# U2S_XLAT.net
KiCad netlist of a schematic drawn in Altium Designer
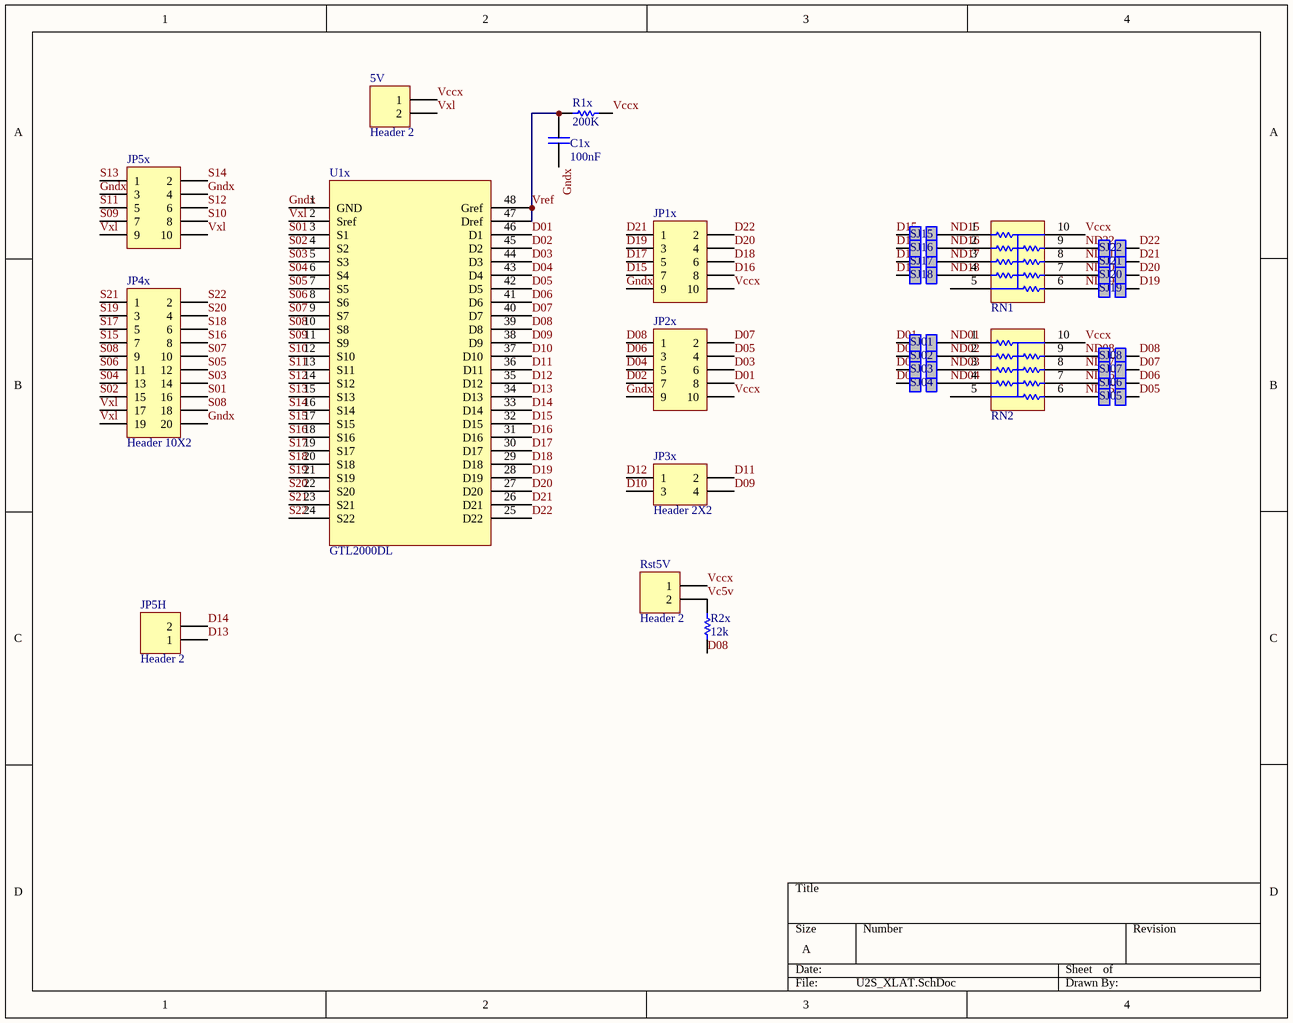
[diagram p0: U2S_XLAT.SchDoc]

(export (version "E")
  (design (tool "Eeschema 10.0.6"))
  (components
    (comp (ref "5V")
      (value "Header 2")
      (footprint "HDR1X2")
      (description "Header, 2-Pin")
      (fields (field (name "PUBLISHER") "Altium Limited"))
      (libsource (lib "") (part "Header 2_1"))
    )
    (comp (ref "C1x")
      (value "100nF")
      (footprint "SMD0603")
      (fields (field (name "Comment") "Capacitor"))
      (libsource (lib "MiscComponents") (part "Capacitor"))
    )
    (comp (ref "JP1x")
      (value "Header 5X2")
      (footprint "HDR2X5")
      (description "Header, 5-Pin, Dual row")
      (fields (field (name "PUBLISHER") "Altium Limited"))
      (libsource (lib "Miscellaneous Connectors") (part "Header 5X2"))
    )
    (comp (ref "JP2x")
      (value "Header 5X2")
      (footprint "HDR2X5")
      (description "Header, 5-Pin, Dual row")
      (fields (field (name "PUBLISHER") "Altium Limited"))
      (libsource (lib "Miscellaneous Connectors") (part "Header 5X2"))
    )
    (comp (ref "JP3x")
      (value "Header 2X2")
      (footprint "HDR2X2")
      (description "Header, 2-Pin, Dual row")
      (fields (field (name "PUBLISHER") "Altium Limited"))
      (libsource (lib "Miscellaneous Connectors") (part "Header 2X2"))
    )
    (comp (ref "JP4x")
      (value "Header 10X2")
      (footprint "HDR2X10")
      (description "Header, 10-Pin, Dual row")
      (fields (field (name "PUBLISHER") "Altium Limited"))
      (libsource (lib "Miscellaneous Connectors") (part "Header 10X2"))
    )
    (comp (ref "JP5H")
      (value "Header 2")
      (footprint "HDR1X2")
      (description "Header, 2-Pin")
      (fields (field (name "PUBLISHER") "Altium Limited"))
      (libsource (lib "Miscellaneous Connectors") (part "Header 2"))
    )
    (comp (ref "JP5x")
      (value "Header 5X2")
      (footprint "HDR2X5")
      (description "Header, 5-Pin, Dual row")
      (fields (field (name "PUBLISHER") "Altium Limited"))
      (libsource (lib "Miscellaneous Connectors") (part "Header 5X2"))
    )
    (comp (ref "R1x")
      (value "200K")
      (footprint "SMD0805")
      (fields (field (name "Comment") "Resistor"))
      (libsource (lib "MiscComponents") (part "Resistor"))
    )
    (comp (ref "R2x")
      (value "12k")
      (footprint "SMD0603")
      (fields (field (name "Comment") "Resistor"))
      (libsource (lib "MiscComponents") (part "Resistor"))
    )
    (comp (ref "RN1") (value "YC158") (footprint "YC158") (libsource (lib "MiscComponents") (part "YC158")))
    (comp (ref "RN2") (value "YC158") (footprint "YC158") (libsource (lib "MiscComponents") (part "YC158")))
    (comp (ref "Rst5V")
      (value "Header 2")
      (footprint "HDR1X2")
      (description "Header, 2-Pin")
      (fields (field (name "PUBLISHER") "Altium Limited"))
      (libsource (lib "") (part "Header 2_1"))
    )
    (comp (ref "SJ01")
      (value "Jumper")
      (footprint "Jumper")
      (description "Solder Jumper")
      (libsource (lib "MiscComponents") (part "Jumper"))
    )
    (comp (ref "SJ02")
      (value "Jumper")
      (footprint "Jumper")
      (description "Solder Jumper")
      (libsource (lib "MiscComponents") (part "Jumper"))
    )
    (comp (ref "SJ03")
      (value "Jumper")
      (footprint "Jumper")
      (description "Solder Jumper")
      (libsource (lib "MiscComponents") (part "Jumper"))
    )
    (comp (ref "SJ04")
      (value "Jumper")
      (footprint "Jumper")
      (description "Solder Jumper")
      (libsource (lib "MiscComponents") (part "Jumper"))
    )
    (comp (ref "SJ05")
      (value "Jumper")
      (footprint "Jumper")
      (description "Solder Jumper")
      (libsource (lib "MiscComponents") (part "Jumper"))
    )
    (comp (ref "SJ06")
      (value "Jumper")
      (footprint "Jumper")
      (description "Solder Jumper")
      (libsource (lib "MiscComponents") (part "Jumper"))
    )
    (comp (ref "SJ07")
      (value "Jumper")
      (footprint "Jumper")
      (description "Solder Jumper")
      (libsource (lib "MiscComponents") (part "Jumper"))
    )
    (comp (ref "SJ08")
      (value "Jumper")
      (footprint "Jumper")
      (description "Solder Jumper")
      (libsource (lib "MiscComponents") (part "Jumper"))
    )
    (comp (ref "SJ15")
      (value "Jumper")
      (footprint "Jumper")
      (description "Solder Jumper")
      (libsource (lib "MiscComponents") (part "Jumper"))
    )
    (comp (ref "SJ16")
      (value "Jumper")
      (footprint "Jumper")
      (description "Solder Jumper")
      (libsource (lib "MiscComponents") (part "Jumper"))
    )
    (comp (ref "SJ17")
      (value "Jumper")
      (footprint "Jumper")
      (description "Solder Jumper")
      (libsource (lib "MiscComponents") (part "Jumper"))
    )
    (comp (ref "SJ18")
      (value "Jumper")
      (footprint "Jumper")
      (description "Solder Jumper")
      (libsource (lib "MiscComponents") (part "Jumper"))
    )
    (comp (ref "SJ19")
      (value "Jumper")
      (footprint "Jumper")
      (description "Solder Jumper")
      (libsource (lib "MiscComponents") (part "Jumper"))
    )
    (comp (ref "SJ20")
      (value "Jumper")
      (footprint "Jumper")
      (description "Solder Jumper")
      (libsource (lib "MiscComponents") (part "Jumper"))
    )
    (comp (ref "SJ21")
      (value "Jumper")
      (footprint "Jumper")
      (description "Solder Jumper")
      (libsource (lib "MiscComponents") (part "Jumper"))
    )
    (comp (ref "SJ22")
      (value "Jumper")
      (footprint "Jumper")
      (description "Solder Jumper")
      (libsource (lib "MiscComponents") (part "Jumper"))
    )
    (comp (ref "U1x")
      (value "GTL2000DL")
      (footprint "SSOP48")
      (libsource (lib "MiscComponents") (part "GTL2000DL"))
    )
  )
  (nets
    (net (code "1") (name "/D01") (class "Default")
      (node (ref "JP2x") (pin "8") (pinfunction "8_8") (pintype "passive"))
      (node (ref "SJ01") (pin "2") (pinfunction "2_2") (pintype "passive"))
      (node (ref "U1x") (pin "46") (pinfunction "D1_46") (pintype "passive"))
    )
    (net (code "2") (name "/D02") (class "Default")
      (node (ref "JP2x") (pin "7") (pinfunction "7_7") (pintype "passive"))
      (node (ref "SJ02") (pin "2") (pinfunction "2_2") (pintype "passive"))
      (node (ref "U1x") (pin "45") (pinfunction "D2_45") (pintype "passive"))
    )
    (net (code "3") (name "/D03") (class "Default")
      (node (ref "JP2x") (pin "6") (pinfunction "6_6") (pintype "passive"))
      (node (ref "SJ03") (pin "2") (pinfunction "2_2") (pintype "passive"))
      (node (ref "U1x") (pin "44") (pinfunction "D3_44") (pintype "passive"))
    )
    (net (code "4") (name "/D04") (class "Default")
      (node (ref "JP2x") (pin "5") (pinfunction "5_5") (pintype "passive"))
      (node (ref "SJ04") (pin "2") (pinfunction "2_2") (pintype "passive"))
      (node (ref "U1x") (pin "43") (pinfunction "D4_43") (pintype "passive"))
    )
    (net (code "5") (name "/D05") (class "Default")
      (node (ref "JP2x") (pin "4") (pinfunction "4_4") (pintype "passive"))
      (node (ref "SJ05") (pin "2") (pinfunction "2_2") (pintype "passive"))
      (node (ref "U1x") (pin "42") (pinfunction "D5_42") (pintype "passive"))
    )
    (net (code "6") (name "/D06") (class "Default")
      (node (ref "JP2x") (pin "3") (pinfunction "3_3") (pintype "passive"))
      (node (ref "SJ06") (pin "2") (pinfunction "2_2") (pintype "passive"))
      (node (ref "U1x") (pin "41") (pinfunction "D6_41") (pintype "passive"))
    )
    (net (code "7") (name "/D07") (class "Default")
      (node (ref "JP2x") (pin "2") (pinfunction "2_2") (pintype "passive"))
      (node (ref "SJ07") (pin "2") (pinfunction "2_2") (pintype "passive"))
      (node (ref "U1x") (pin "40") (pinfunction "D7_40") (pintype "passive"))
    )
    (net (code "8") (name "/D08") (class "Default")
      (node (ref "JP2x") (pin "1") (pinfunction "1_1") (pintype "passive"))
      (node (ref "R2x") (pin "1") (pinfunction "1_1") (pintype "passive"))
      (node (ref "SJ08") (pin "2") (pinfunction "2_2") (pintype "passive"))
      (node (ref "U1x") (pin "39") (pinfunction "D8_39") (pintype "passive"))
    )
    (net (code "9") (name "/D09") (class "Default")
      (node (ref "JP3x") (pin "4") (pinfunction "4_4") (pintype "passive"))
      (node (ref "U1x") (pin "38") (pinfunction "D9_38") (pintype "passive"))
    )
    (net (code "10") (name "/D10") (class "Default")
      (node (ref "JP3x") (pin "3") (pinfunction "3_3") (pintype "passive"))
      (node (ref "U1x") (pin "37") (pinfunction "D10_37") (pintype "passive"))
    )
    (net (code "11") (name "/D11") (class "Default")
      (node (ref "JP3x") (pin "2") (pinfunction "2_2") (pintype "passive"))
      (node (ref "U1x") (pin "36") (pinfunction "D11_36") (pintype "passive"))
    )
    (net (code "12") (name "/D12") (class "Default")
      (node (ref "JP3x") (pin "1") (pinfunction "1_1") (pintype "passive"))
      (node (ref "U1x") (pin "35") (pinfunction "D12_35") (pintype "passive"))
    )
    (net (code "13") (name "/D13") (class "Default")
      (node (ref "JP5H") (pin "1") (pinfunction "1_1") (pintype "passive"))
      (node (ref "U1x") (pin "34") (pinfunction "D13_34") (pintype "passive"))
    )
    (net (code "14") (name "/D14") (class "Default")
      (node (ref "JP5H") (pin "2") (pinfunction "2_2") (pintype "passive"))
      (node (ref "U1x") (pin "33") (pinfunction "D14_33") (pintype "passive"))
    )
    (net (code "15") (name "/D15") (class "Default")
      (node (ref "JP1x") (pin "7") (pinfunction "7_7") (pintype "passive"))
      (node (ref "SJ15") (pin "2") (pinfunction "2_2") (pintype "passive"))
      (node (ref "U1x") (pin "32") (pinfunction "D15_32") (pintype "passive"))
    )
    (net (code "16") (name "/D16") (class "Default")
      (node (ref "JP1x") (pin "8") (pinfunction "8_8") (pintype "passive"))
      (node (ref "SJ16") (pin "2") (pinfunction "2_2") (pintype "passive"))
      (node (ref "U1x") (pin "31") (pinfunction "D16_31") (pintype "passive"))
    )
    (net (code "17") (name "/D17") (class "Default")
      (node (ref "JP1x") (pin "5") (pinfunction "5_5") (pintype "passive"))
      (node (ref "SJ17") (pin "2") (pinfunction "2_2") (pintype "passive"))
      (node (ref "U1x") (pin "30") (pinfunction "D17_30") (pintype "passive"))
    )
    (net (code "18") (name "/D18") (class "Default")
      (node (ref "JP1x") (pin "6") (pinfunction "6_6") (pintype "passive"))
      (node (ref "SJ18") (pin "2") (pinfunction "2_2") (pintype "passive"))
      (node (ref "U1x") (pin "29") (pinfunction "D18_29") (pintype "passive"))
    )
    (net (code "19") (name "/D19") (class "Default")
      (node (ref "JP1x") (pin "3") (pinfunction "3_3") (pintype "passive"))
      (node (ref "SJ19") (pin "2") (pinfunction "2_2") (pintype "passive"))
      (node (ref "U1x") (pin "28") (pinfunction "D19_28") (pintype "passive"))
    )
    (net (code "20") (name "/D20") (class "Default")
      (node (ref "JP1x") (pin "4") (pinfunction "4_4") (pintype "passive"))
      (node (ref "SJ20") (pin "2") (pinfunction "2_2") (pintype "passive"))
      (node (ref "U1x") (pin "27") (pinfunction "D20_27") (pintype "passive"))
    )
    (net (code "21") (name "/D21") (class "Default")
      (node (ref "JP1x") (pin "1") (pinfunction "1_1") (pintype "passive"))
      (node (ref "SJ21") (pin "2") (pinfunction "2_2") (pintype "passive"))
      (node (ref "U1x") (pin "26") (pinfunction "D21_26") (pintype "passive"))
    )
    (net (code "22") (name "/D22") (class "Default")
      (node (ref "JP1x") (pin "2") (pinfunction "2_2") (pintype "passive"))
      (node (ref "SJ22") (pin "2") (pinfunction "2_2") (pintype "passive"))
      (node (ref "U1x") (pin "25") (pinfunction "D22_25") (pintype "passive"))
    )
    (net (code "23") (name "/Gndx") (class "Default")
      (node (ref "C1x") (pin "1") (pinfunction "1_1") (pintype "passive"))
      (node (ref "JP1x") (pin "9") (pinfunction "9_9") (pintype "passive"))
      (node (ref "JP2x") (pin "9") (pinfunction "9_9") (pintype "passive"))
      (node (ref "JP4x") (pin "20") (pinfunction "20_20") (pintype "passive"))
      (node (ref "JP5x") (pin "3") (pinfunction "3_3") (pintype "passive"))
      (node (ref "JP5x") (pin "4") (pinfunction "4_4") (pintype "passive"))
      (node (ref "U1x") (pin "1") (pinfunction "GND_1") (pintype "passive"))
    )
    (net (code "24") (name "/ND01") (class "Default")
      (node (ref "RN2") (pin "1") (pinfunction "1_1") (pintype "passive"))
      (node (ref "SJ01") (pin "1") (pinfunction "1_1") (pintype "passive"))
    )
    (net (code "25") (name "/ND02") (class "Default")
      (node (ref "RN2") (pin "2") (pinfunction "2_2") (pintype "passive"))
      (node (ref "SJ02") (pin "1") (pinfunction "1_1") (pintype "passive"))
    )
    (net (code "26") (name "/ND03") (class "Default")
      (node (ref "RN2") (pin "3") (pinfunction "3_3") (pintype "passive"))
      (node (ref "SJ03") (pin "1") (pinfunction "1_1") (pintype "passive"))
    )
    (net (code "27") (name "/ND04") (class "Default")
      (node (ref "RN2") (pin "4") (pinfunction "4_4") (pintype "passive"))
      (node (ref "SJ04") (pin "1") (pinfunction "1_1") (pintype "passive"))
    )
    (net (code "28") (name "/ND05") (class "Default")
      (node (ref "RN2") (pin "6") (pinfunction "6_6") (pintype "passive"))
      (node (ref "SJ05") (pin "1") (pinfunction "1_1") (pintype "passive"))
    )
    (net (code "29") (name "/ND06") (class "Default")
      (node (ref "RN2") (pin "7") (pinfunction "7_7") (pintype "passive"))
      (node (ref "SJ06") (pin "1") (pinfunction "1_1") (pintype "passive"))
    )
    (net (code "30") (name "/ND07") (class "Default")
      (node (ref "RN2") (pin "8") (pinfunction "8_8") (pintype "passive"))
      (node (ref "SJ07") (pin "1") (pinfunction "1_1") (pintype "passive"))
    )
    (net (code "31") (name "/ND08") (class "Default")
      (node (ref "RN2") (pin "9") (pinfunction "9_9") (pintype "passive"))
      (node (ref "SJ08") (pin "1") (pinfunction "1_1") (pintype "passive"))
    )
    (net (code "32") (name "/ND15") (class "Default")
      (node (ref "RN1") (pin "1") (pinfunction "1_1") (pintype "passive"))
      (node (ref "SJ15") (pin "1") (pinfunction "1_1") (pintype "passive"))
    )
    (net (code "33") (name "/ND16") (class "Default")
      (node (ref "RN1") (pin "2") (pinfunction "2_2") (pintype "passive"))
      (node (ref "SJ16") (pin "1") (pinfunction "1_1") (pintype "passive"))
    )
    (net (code "34") (name "/ND17") (class "Default")
      (node (ref "RN1") (pin "3") (pinfunction "3_3") (pintype "passive"))
      (node (ref "SJ17") (pin "1") (pinfunction "1_1") (pintype "passive"))
    )
    (net (code "35") (name "/ND18") (class "Default")
      (node (ref "RN1") (pin "4") (pinfunction "4_4") (pintype "passive"))
      (node (ref "SJ18") (pin "1") (pinfunction "1_1") (pintype "passive"))
    )
    (net (code "36") (name "/ND19") (class "Default")
      (node (ref "RN1") (pin "6") (pinfunction "6_6") (pintype "passive"))
      (node (ref "SJ19") (pin "1") (pinfunction "1_1") (pintype "passive"))
    )
    (net (code "37") (name "/ND20") (class "Default")
      (node (ref "RN1") (pin "7") (pinfunction "7_7") (pintype "passive"))
      (node (ref "SJ20") (pin "1") (pinfunction "1_1") (pintype "passive"))
    )
    (net (code "38") (name "/ND21") (class "Default")
      (node (ref "RN1") (pin "8") (pinfunction "8_8") (pintype "passive"))
      (node (ref "SJ21") (pin "1") (pinfunction "1_1") (pintype "passive"))
    )
    (net (code "39") (name "/ND22") (class "Default")
      (node (ref "RN1") (pin "9") (pinfunction "9_9") (pintype "passive"))
      (node (ref "SJ22") (pin "1") (pinfunction "1_1") (pintype "passive"))
    )
    (net (code "40") (name "/S01") (class "Default")
      (node (ref "JP4x") (pin "16") (pinfunction "16_16") (pintype "passive"))
      (node (ref "U1x") (pin "3") (pinfunction "S1_3") (pintype "passive"))
    )
    (net (code "41") (name "/S02") (class "Default")
      (node (ref "JP4x") (pin "15") (pinfunction "15_15") (pintype "passive"))
      (node (ref "U1x") (pin "4") (pinfunction "S2_4") (pintype "passive"))
    )
    (net (code "42") (name "/S03") (class "Default")
      (node (ref "JP4x") (pin "14") (pinfunction "14_14") (pintype "passive"))
      (node (ref "U1x") (pin "5") (pinfunction "S3_5") (pintype "passive"))
    )
    (net (code "43") (name "/S04") (class "Default")
      (node (ref "JP4x") (pin "13") (pinfunction "13_13") (pintype "passive"))
      (node (ref "U1x") (pin "6") (pinfunction "S4_6") (pintype "passive"))
    )
    (net (code "44") (name "/S05") (class "Default")
      (node (ref "JP4x") (pin "12") (pinfunction "12_12") (pintype "passive"))
      (node (ref "U1x") (pin "7") (pinfunction "S5_7") (pintype "passive"))
    )
    (net (code "45") (name "/S06") (class "Default")
      (node (ref "JP4x") (pin "11") (pinfunction "11_11") (pintype "passive"))
      (node (ref "U1x") (pin "8") (pinfunction "S6_8") (pintype "passive"))
    )
    (net (code "46") (name "/S07") (class "Default")
      (node (ref "JP4x") (pin "10") (pinfunction "10_10") (pintype "passive"))
      (node (ref "U1x") (pin "9") (pinfunction "S7_9") (pintype "passive"))
    )
    (net (code "47") (name "/S08") (class "Default")
      (node (ref "JP4x") (pin "18") (pinfunction "18_18") (pintype "passive"))
      (node (ref "JP4x") (pin "9") (pinfunction "9_9") (pintype "passive"))
      (node (ref "U1x") (pin "10") (pinfunction "S8_10") (pintype "passive"))
    )
    (net (code "48") (name "/S09") (class "Default")
      (node (ref "JP5x") (pin "7") (pinfunction "7_7") (pintype "passive"))
      (node (ref "U1x") (pin "11") (pinfunction "S9_11") (pintype "passive"))
    )
    (net (code "49") (name "/S10") (class "Default")
      (node (ref "JP5x") (pin "8") (pinfunction "8_8") (pintype "passive"))
      (node (ref "U1x") (pin "12") (pinfunction "S10_12") (pintype "passive"))
    )
    (net (code "50") (name "/S11") (class "Default")
      (node (ref "JP5x") (pin "5") (pinfunction "5_5") (pintype "passive"))
      (node (ref "U1x") (pin "13") (pinfunction "S11_13") (pintype "passive"))
    )
    (net (code "51") (name "/S12") (class "Default")
      (node (ref "JP5x") (pin "6") (pinfunction "6_6") (pintype "passive"))
      (node (ref "U1x") (pin "14") (pinfunction "S12_14") (pintype "passive"))
    )
    (net (code "52") (name "/S13") (class "Default")
      (node (ref "JP5x") (pin "1") (pinfunction "1_1") (pintype "passive"))
      (node (ref "U1x") (pin "15") (pinfunction "S13_15") (pintype "passive"))
    )
    (net (code "53") (name "/S14") (class "Default")
      (node (ref "JP5x") (pin "2") (pinfunction "2_2") (pintype "passive"))
      (node (ref "U1x") (pin "16") (pinfunction "S14_16") (pintype "passive"))
    )
    (net (code "54") (name "/S15") (class "Default")
      (node (ref "JP4x") (pin "7") (pinfunction "7_7") (pintype "passive"))
      (node (ref "U1x") (pin "17") (pinfunction "S15_17") (pintype "passive"))
    )
    (net (code "55") (name "/S16") (class "Default")
      (node (ref "JP4x") (pin "8") (pinfunction "8_8") (pintype "passive"))
      (node (ref "U1x") (pin "18") (pinfunction "S16_18") (pintype "passive"))
    )
    (net (code "56") (name "/S17") (class "Default")
      (node (ref "JP4x") (pin "5") (pinfunction "5_5") (pintype "passive"))
      (node (ref "U1x") (pin "19") (pinfunction "S17_19") (pintype "passive"))
    )
    (net (code "57") (name "/S18") (class "Default")
      (node (ref "JP4x") (pin "6") (pinfunction "6_6") (pintype "passive"))
      (node (ref "U1x") (pin "20") (pinfunction "S18_20") (pintype "passive"))
    )
    (net (code "58") (name "/S19") (class "Default")
      (node (ref "JP4x") (pin "3") (pinfunction "3_3") (pintype "passive"))
      (node (ref "U1x") (pin "21") (pinfunction "S19_21") (pintype "passive"))
    )
    (net (code "59") (name "/S20") (class "Default")
      (node (ref "JP4x") (pin "4") (pinfunction "4_4") (pintype "passive"))
      (node (ref "U1x") (pin "22") (pinfunction "S20_22") (pintype "passive"))
    )
    (net (code "60") (name "/S21") (class "Default")
      (node (ref "JP4x") (pin "1") (pinfunction "1_1") (pintype "passive"))
      (node (ref "U1x") (pin "23") (pinfunction "S21_23") (pintype "passive"))
    )
    (net (code "61") (name "/S22") (class "Default")
      (node (ref "JP4x") (pin "2") (pinfunction "2_2") (pintype "passive"))
      (node (ref "U1x") (pin "24") (pinfunction "S22_24") (pintype "passive"))
    )
    (net (code "62") (name "/Vc5v") (class "Default")
      (node (ref "R2x") (pin "2") (pinfunction "2_2") (pintype "passive"))
      (node (ref "Rst5V") (pin "2") (pinfunction "2_2") (pintype "passive"))
    )
    (net (code "63") (name "/Vccx") (class "Default")
      (node (ref "5V") (pin "1") (pinfunction "1_1") (pintype "passive"))
      (node (ref "JP1x") (pin "10") (pinfunction "10_10") (pintype "passive"))
      (node (ref "JP2x") (pin "10") (pinfunction "10_10") (pintype "passive"))
      (node (ref "R1x") (pin "2") (pinfunction "2_2") (pintype "passive"))
      (node (ref "RN1") (pin "10") (pinfunction "10_10") (pintype "passive"))
      (node (ref "RN2") (pin "10") (pinfunction "10_10") (pintype "passive"))
      (node (ref "Rst5V") (pin "1") (pinfunction "1_1") (pintype "passive"))
    )
    (net (code "64") (name "/Vref") (class "Default")
      (node (ref "C1x") (pin "2") (pinfunction "2_2") (pintype "passive"))
      (node (ref "R1x") (pin "1") (pinfunction "1_1") (pintype "passive"))
      (node (ref "U1x") (pin "47") (pinfunction "Dref_47") (pintype "passive"))
      (node (ref "U1x") (pin "48") (pinfunction "Gref_48") (pintype "passive"))
    )
    (net (code "65") (name "/Vxl") (class "Default")
      (node (ref "5V") (pin "2") (pinfunction "2_2") (pintype "passive"))
      (node (ref "JP4x") (pin "17") (pinfunction "17_17") (pintype "passive"))
      (node (ref "JP4x") (pin "19") (pinfunction "19_19") (pintype "passive"))
      (node (ref "JP5x") (pin "10") (pinfunction "10_10") (pintype "passive"))
      (node (ref "JP5x") (pin "9") (pinfunction "9_9") (pintype "passive"))
      (node (ref "U1x") (pin "2") (pinfunction "Sref_2") (pintype "passive"))
    )
    (net (code "66") (name "unconnected-(RN1-Pad5)") (class "Default")
      (node (ref "RN1") (pin "5") (pinfunction "5_5") (pintype "passive"))
    )
    (net (code "67") (name "unconnected-(RN2-Pad5)") (class "Default")
      (node (ref "RN2") (pin "5") (pinfunction "5_5") (pintype "passive"))
    )
  )
)
